# eps_flash.net
KiCad netlist of a schematic drawn in Altium Designer
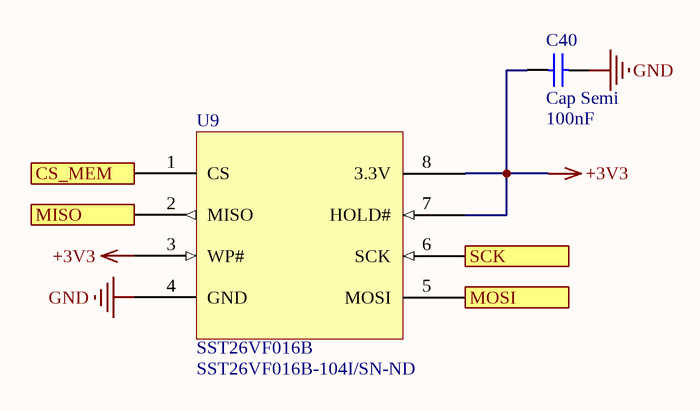
[diagram p0: eps_flash.SchDoc]

(export (version "E")
  (design (tool "Eeschema 10.0.6"))
  (components
    (comp (ref "C40")
      (value "Cap Semi")
      (footprint "1608[0603]")
      (description "Capacitor (Semiconductor SIM Model)")
      (fields (field (name "ALTIUM_VALUE") "100nF") (field (name "PUBLISHER") "Altium Limited"))
      (libsource (lib "Miscellaneous Devices") (part "Cap Semi"))
    )
    (comp (ref "U9")
      (value "SST26VF016B")
      (description "2.5V/3.0V 16 Mbit Serial Quad I/O (SQI) Flash Memory")
      (fields (field (name "SUPPLIER PART NUMBER 1") "SST26VF016B-104I/SN-ND"))
      (libsource (lib "heron-general") (part "SST26VF016B"))
    )
  )
  (nets
    (net (code "1") (name "+3V3") (class "Default")
      (node (ref "C40") (pin "1") (pinfunction "1_1") (pintype "passive"))
      (node (ref "U9") (pin "3") (pinfunction "WP#_3") (pintype "input"))
      (node (ref "U9") (pin "7") (pinfunction "HOLD#_7") (pintype "input"))
      (node (ref "U9") (pin "8") (pinfunction "3.3V_8") (pintype "power_in"))
    )
    (net (code "2") (name "/CS_MEM") (class "Default")
      (node (ref "U9") (pin "1") (pinfunction "CS_1") (pintype "passive"))
    )
    (net (code "3") (name "/MISO") (class "Default")
      (node (ref "U9") (pin "2") (pinfunction "MISO_2") (pintype "output"))
    )
    (net (code "4") (name "/MOSI") (class "Default")
      (node (ref "U9") (pin "5") (pinfunction "MOSI_5") (pintype "passive"))
    )
    (net (code "5") (name "/SCK") (class "Default")
      (node (ref "U9") (pin "6") (pinfunction "SCK_6") (pintype "input"))
    )
    (net (code "6") (name "GND") (class "Default")
      (node (ref "C40") (pin "2") (pinfunction "2_2") (pintype "passive"))
      (node (ref "U9") (pin "4") (pinfunction "GND_4") (pintype "power_in"))
    )
  )
)
